# digital_clock_no_resistors.net
KiCad netlist of a schematic drawn in EasyEDA
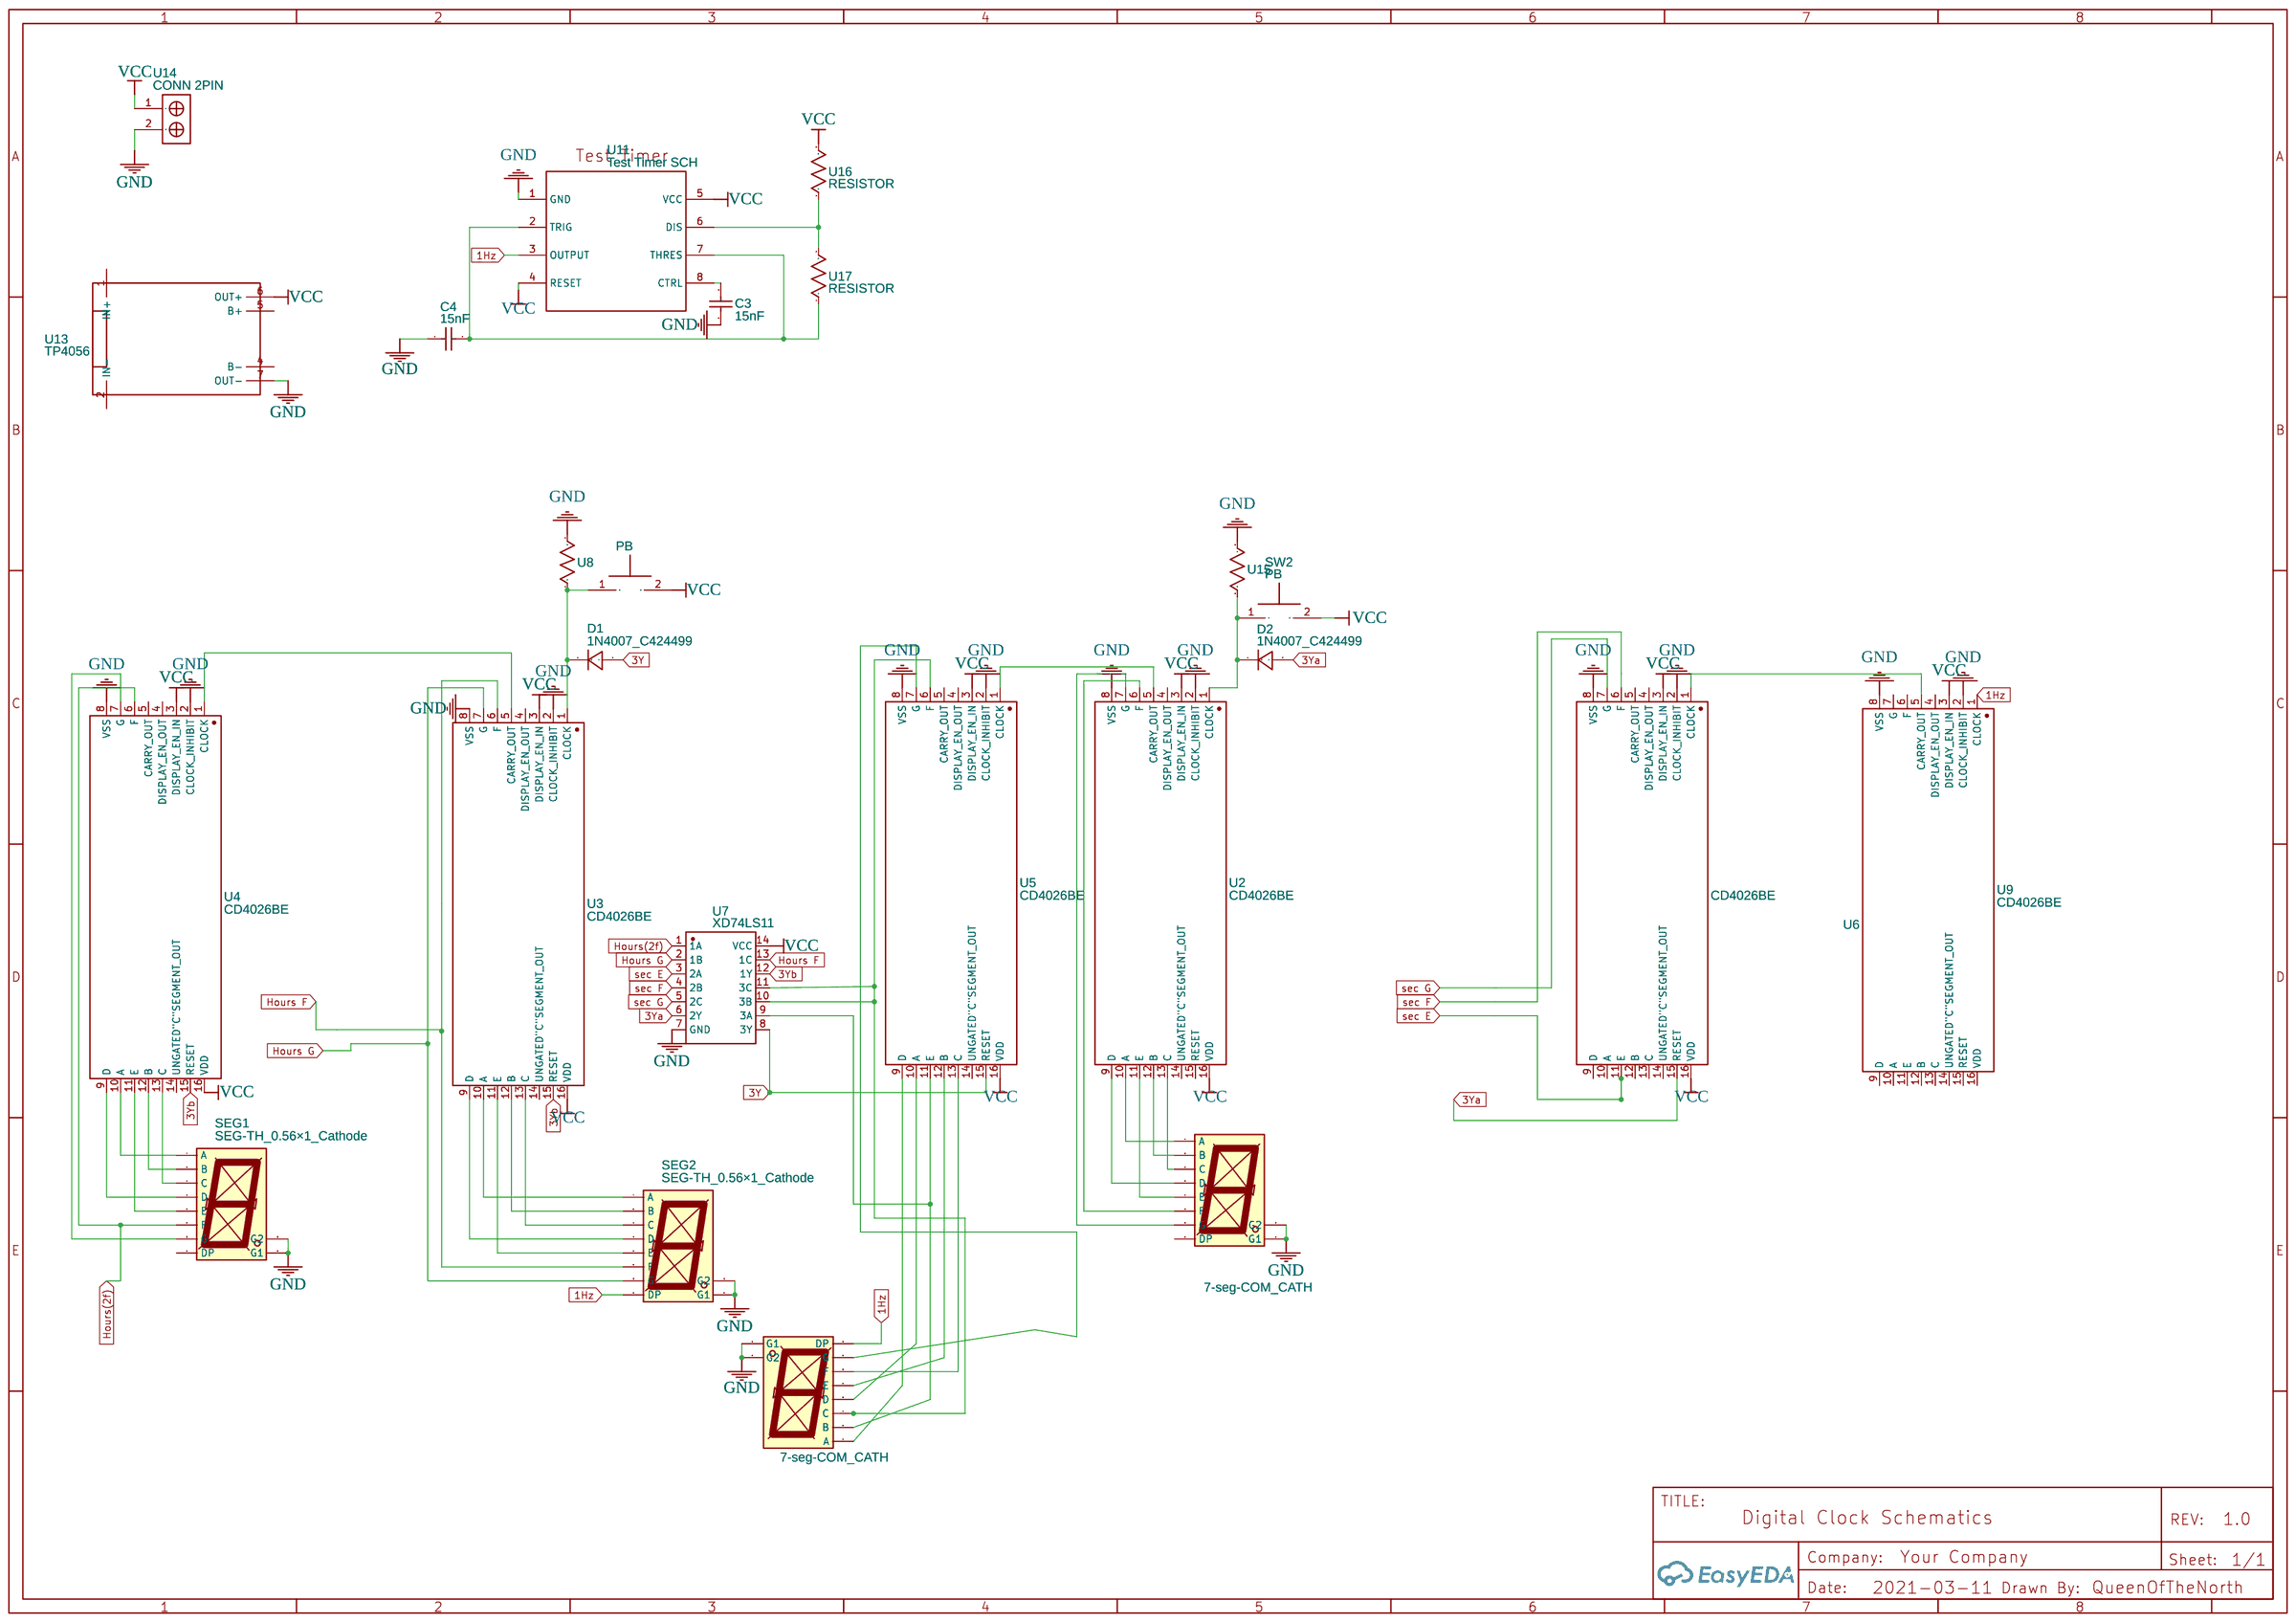
[diagram p0: schematic sheet]

(export (version "E")
  (design (tool "Eeschema 10.0.6"))
  (components
    (comp (ref "C3")
      (value "15nF")
      (fields
        (field (name "BOM_Manufacturer Part") "Capacitor15nf100v")
        (field (name "BOM_Supplier Part") "C26191")
      )
      (libsource (lib "") (part "CAPACITOR15NF100V"))
    )
    (comp (ref "C4")
      (value "15nF")
      (fields
        (field (name "BOM_Manufacturer Part") "Capacitor15nf100v")
        (field (name "BOM_Supplier Part") "C26191")
      )
      (libsource (lib "") (part "CAPACITOR15NF100V_1"))
    )
    (comp (ref "D1")
      (value "1N4007_C424499")
      (fields (field (name "BOM_Manufacturer Part") "1N4007") (field (name "BOM_Supplier Part") "C424499"))
      (libsource (lib "") (part "1N4007_C424499"))
    )
    (comp (ref "D2")
      (value "1N4007_C424499")
      (fields (field (name "BOM_Manufacturer Part") "1N4007") (field (name "BOM_Supplier Part") "C424499"))
      (libsource (lib "") (part "1N4007_C424499"))
    )
    (comp (ref "SEG1")
      (value "SEG-TH_0.56×1_Cathode")
      (fields (field (name "BOM_Supplier Part") "C8093"))
      (libsource (lib "") (part "SEG-TH_0.56×1_Cathode_1"))
    )
    (comp (ref "SEG2")
      (value "SEG-TH_0.56×1_Cathode")
      (fields (field (name "BOM_Supplier Part") "C8093"))
      (libsource (lib "") (part "SEG-TH_0.56×1_Cathode_1"))
    )
    (comp (ref "SEG3")
      (value "7-seg-COM_CATH")
      (fields (field (name "BOM_Supplier Part") "C8093"))
      (libsource (lib "") (part "SEG-TH_0.56×1_Cathode"))
    )
    (comp (ref "SEG4")
      (value "7-seg-COM_CATH")
      (fields (field (name "BOM_Supplier Part") "C8093"))
      (libsource (lib "") (part "SEG-TH_0.56×1_Cathode_1"))
    )
    (comp (ref "SW1")
      (value "PB")
      (fields (field (name "BOM_Manufacturer Part") "Push button"))
      (libsource (lib "") (part "PB"))
    )
    (comp (ref "SW2")
      (value "PB")
      (fields (field (name "BOM_Manufacturer Part") "Push button"))
      (libsource (lib "") (part "PB"))
    )
    (comp (ref "U2")
      (value "CD4026BE")
      (fields (field (name "BOM_Supplier Part") "C89909"))
      (libsource (lib "") (part "CD4026BE"))
    )
    (comp (ref "U3")
      (value "CD4026BE")
      (fields (field (name "BOM_Supplier Part") "C89909"))
      (libsource (lib "") (part "CD4026BE"))
    )
    (comp (ref "U4")
      (value "CD4026BE")
      (fields (field (name "BOM_Supplier Part") "C89909"))
      (libsource (lib "") (part "CD4026BE"))
    )
    (comp (ref "U5")
      (value "CD4026BE")
      (fields (field (name "BOM_Supplier Part") "C89909"))
      (libsource (lib "") (part "CD4026BE"))
    )
    (comp (ref "U6")
      (value "CD4026BE")
      (fields (field (name "BOM_Supplier Part") "C89909"))
      (libsource (lib "") (part "CD4026BE"))
    )
    (comp (ref "U7")
      (value "XD74LS11")
      (fields (field (name "BOM_Supplier Part") "C521167"))
      (libsource (lib "") (part "XD74LS11"))
    )
    (comp (ref "U8")
      (value "RESISTOR")
      (fields (field (name "BOM_Manufacturer Part") "0.4W 1% RESISTOR"))
      (libsource (lib "") (part "RESISTOR"))
    )
    (comp (ref "U9")
      (value "CD4026BE")
      (fields (field (name "BOM_Supplier Part") "C89909"))
      (libsource (lib "") (part "CD4026BE"))
    )
    (comp (ref "U11")
      (value "Test Timer SCH")
      (fields (field (name "BOM_Manufacturer Part") "555 Timer"))
      (libsource (lib "") (part "Test Timer SCH"))
    )
    (comp (ref "U13")
      (value "TP4056")
      (fields (field (name "BOM_Manufacturer Part") "TP4056-protect"))
      (libsource (lib "") (part "TP4056"))
    )
    (comp (ref "U14")
      (value "CONN 2PIN")
      (fields
        (field (name "BOM_Manufacturer Part") "Terminal Block")
        (field (name "BOM_Supplier Part") "undefined")
      )
      (libsource (lib "") (part "CONN 2PIN"))
    )
    (comp (ref "U15")
      (value "RESISTOR")
      (fields (field (name "BOM_Manufacturer Part") "0.4W 1% RESISTOR"))
      (libsource (lib "") (part "RESISTOR"))
    )
    (comp (ref "U16")
      (value "RESISTOR")
      (fields (field (name "BOM_Manufacturer Part") "0.4W 1% RESISTOR"))
      (libsource (lib "") (part "RESISTOR"))
    )
    (comp (ref "U17")
      (value "RESISTOR")
      (fields (field (name "BOM_Manufacturer Part") "0.4W 1% RESISTOR"))
      (libsource (lib "") (part "RESISTOR"))
    )
  )
  (nets
    (net (code "1") (name "1Hz") (class "Default")
      (node (ref "SEG2") (pin "5") (pinfunction "DP_5") (pintype "unspecified"))
      (node (ref "SEG3") (pin "5") (pinfunction "DP_5") (pintype "unspecified"))
      (node (ref "U11") (pin "3") (pinfunction "OUTPUT_3") (pintype "unspecified"))
      (node (ref "U9") (pin "1") (pinfunction "CLOCK_1") (pintype "unspecified"))
    )
    (net (code "2") (name "3Y") (class "Default")
      (node (ref "D1") (pin "2") (pinfunction "A_2") (pintype "unspecified"))
      (node (ref "U5") (pin "15") (pinfunction "RESET_15") (pintype "unspecified"))
      (node (ref "U7") (pin "8") (pinfunction "3Y_8") (pintype "unspecified"))
    )
    (net (code "3") (name "3Ya") (class "Default")
      (node (ref "D2") (pin "2") (pinfunction "A_2") (pintype "unspecified"))
      (node (ref "U6") (pin "15") (pinfunction "RESET_15") (pintype "unspecified"))
      (node (ref "U7") (pin "6") (pinfunction "2Y_6") (pintype "unspecified"))
    )
    (net (code "4") (name "3Yb") (class "Default")
      (node (ref "U3") (pin "15") (pinfunction "RESET_15") (pintype "unspecified"))
      (node (ref "U4") (pin "15") (pinfunction "RESET_15") (pintype "unspecified"))
      (node (ref "U7") (pin "12") (pinfunction "1Y_12") (pintype "unspecified"))
    )
    (net (code "5") (name "GND") (class "Default")
      (node (ref "C3") (pin "1") (pinfunction "1_1") (pintype "input"))
      (node (ref "C4") (pin "1") (pinfunction "1_1") (pintype "input"))
      (node (ref "SEG1") (pin "3") (pinfunction "G1_3") (pintype "unspecified"))
      (node (ref "SEG1") (pin "8") (pinfunction "G2_8") (pintype "unspecified"))
      (node (ref "SEG2") (pin "3") (pinfunction "G1_3") (pintype "unspecified"))
      (node (ref "SEG2") (pin "8") (pinfunction "G2_8") (pintype "unspecified"))
      (node (ref "SEG3") (pin "3") (pinfunction "G1_3") (pintype "unspecified"))
      (node (ref "SEG3") (pin "8") (pinfunction "G2_8") (pintype "unspecified"))
      (node (ref "SEG4") (pin "3") (pinfunction "G1_3") (pintype "unspecified"))
      (node (ref "SEG4") (pin "8") (pinfunction "G2_8") (pintype "unspecified"))
      (node (ref "U11") (pin "1") (pinfunction "GND_1") (pintype "unspecified"))
      (node (ref "U13") (pin "7") (pinfunction "OUT-_7") (pintype "unspecified"))
      (node (ref "U14") (pin "2") (pinfunction "2_2") (pintype "unspecified"))
      (node (ref "U15") (pin "2") (pinfunction "2_2") (pintype "unspecified"))
      (node (ref "U2") (pin "2") (pinfunction "CLOCK_INHIBIT_2") (pintype "unspecified"))
      (node (ref "U2") (pin "8") (pinfunction "VSS_8") (pintype "unspecified"))
      (node (ref "U3") (pin "2") (pinfunction "CLOCK_INHIBIT_2") (pintype "unspecified"))
      (node (ref "U3") (pin "8") (pinfunction "VSS_8") (pintype "unspecified"))
      (node (ref "U4") (pin "2") (pinfunction "CLOCK_INHIBIT_2") (pintype "unspecified"))
      (node (ref "U4") (pin "8") (pinfunction "VSS_8") (pintype "unspecified"))
      (node (ref "U5") (pin "2") (pinfunction "CLOCK_INHIBIT_2") (pintype "unspecified"))
      (node (ref "U5") (pin "8") (pinfunction "VSS_8") (pintype "unspecified"))
      (node (ref "U6") (pin "2") (pinfunction "CLOCK_INHIBIT_2") (pintype "unspecified"))
      (node (ref "U6") (pin "8") (pinfunction "VSS_8") (pintype "unspecified"))
      (node (ref "U7") (pin "7") (pinfunction "GND_7") (pintype "unspecified"))
      (node (ref "U8") (pin "2") (pinfunction "2_2") (pintype "unspecified"))
      (node (ref "U9") (pin "2") (pinfunction "CLOCK_INHIBIT_2") (pintype "unspecified"))
      (node (ref "U9") (pin "8") (pinfunction "VSS_8") (pintype "unspecified"))
    )
    (net (code "6") (name "Hours F") (class "Default")
      (node (ref "SEG2") (pin "9") (pinfunction "F_9") (pintype "unspecified"))
      (node (ref "U3") (pin "6") (pinfunction "F_6") (pintype "unspecified"))
      (node (ref "U7") (pin "13") (pinfunction "1C_13") (pintype "unspecified"))
    )
    (net (code "7") (name "Hours G") (class "Default")
      (node (ref "SEG2") (pin "10") (pinfunction "G_10") (pintype "unspecified"))
      (node (ref "U3") (pin "7") (pinfunction "G_7") (pintype "unspecified"))
      (node (ref "U7") (pin "2") (pinfunction "1B_2") (pintype "unspecified"))
    )
    (net (code "8") (name "Hours(2f)") (class "Default")
      (node (ref "SEG1") (pin "9") (pinfunction "F_9") (pintype "unspecified"))
      (node (ref "U4") (pin "6") (pinfunction "F_6") (pintype "unspecified"))
      (node (ref "U7") (pin "1") (pinfunction "1A_1") (pintype "unspecified"))
    )
    (net (code "9") (name "Net-(D1-C)") (class "Default")
      (node (ref "D1") (pin "1") (pinfunction "C_1") (pintype "unspecified"))
      (node (ref "SW1") (pin "1") (pinfunction "1_1") (pintype "unspecified"))
      (node (ref "U3") (pin "1") (pinfunction "CLOCK_1") (pintype "unspecified"))
      (node (ref "U8") (pin "1") (pinfunction "1_1") (pintype "unspecified"))
    )
    (net (code "10") (name "Net-(D2-C)") (class "Default")
      (node (ref "D2") (pin "1") (pinfunction "C_1") (pintype "unspecified"))
      (node (ref "SW2") (pin "1") (pinfunction "1_1") (pintype "unspecified"))
      (node (ref "U15") (pin "1") (pinfunction "1_1") (pintype "unspecified"))
      (node (ref "U2") (pin "1") (pinfunction "CLOCK_1") (pintype "unspecified"))
    )
    (net (code "11") (name "Net-(SEG1-A)") (class "Default")
      (node (ref "SEG1") (pin "7") (pinfunction "A_7") (pintype "unspecified"))
      (node (ref "U4") (pin "10") (pinfunction "A_10") (pintype "unspecified"))
    )
    (net (code "12") (name "Net-(SEG1-B)") (class "Default")
      (node (ref "SEG1") (pin "6") (pinfunction "B_6") (pintype "unspecified"))
      (node (ref "U4") (pin "12") (pinfunction "B_12") (pintype "unspecified"))
    )
    (net (code "13") (name "Net-(SEG1-C)") (class "Default")
      (node (ref "SEG1") (pin "4") (pinfunction "C_4") (pintype "unspecified"))
      (node (ref "U4") (pin "13") (pinfunction "C_13") (pintype "unspecified"))
    )
    (net (code "14") (name "Net-(SEG1-D)") (class "Default")
      (node (ref "SEG1") (pin "2") (pinfunction "D_2") (pintype "unspecified"))
      (node (ref "U4") (pin "9") (pinfunction "D_9") (pintype "unspecified"))
    )
    (net (code "15") (name "Net-(SEG1-E)") (class "Default")
      (node (ref "SEG1") (pin "1") (pinfunction "E_1") (pintype "unspecified"))
      (node (ref "U4") (pin "11") (pinfunction "E_11") (pintype "unspecified"))
    )
    (net (code "16") (name "Net-(SEG1-G)") (class "Default")
      (node (ref "SEG1") (pin "10") (pinfunction "G_10") (pintype "unspecified"))
      (node (ref "U4") (pin "7") (pinfunction "G_7") (pintype "unspecified"))
    )
    (net (code "17") (name "Net-(SEG2-A)") (class "Default")
      (node (ref "SEG2") (pin "7") (pinfunction "A_7") (pintype "unspecified"))
      (node (ref "U3") (pin "10") (pinfunction "A_10") (pintype "unspecified"))
    )
    (net (code "18") (name "Net-(SEG2-B)") (class "Default")
      (node (ref "SEG2") (pin "6") (pinfunction "B_6") (pintype "unspecified"))
      (node (ref "U3") (pin "12") (pinfunction "B_12") (pintype "unspecified"))
    )
    (net (code "19") (name "Net-(SEG2-C)") (class "Default")
      (node (ref "SEG2") (pin "4") (pinfunction "C_4") (pintype "unspecified"))
      (node (ref "U3") (pin "13") (pinfunction "C_13") (pintype "unspecified"))
    )
    (net (code "20") (name "Net-(SEG2-D)") (class "Default")
      (node (ref "SEG2") (pin "2") (pinfunction "D_2") (pintype "unspecified"))
      (node (ref "U3") (pin "9") (pinfunction "D_9") (pintype "unspecified"))
    )
    (net (code "21") (name "Net-(SEG2-E)") (class "Default")
      (node (ref "SEG2") (pin "1") (pinfunction "E_1") (pintype "unspecified"))
      (node (ref "U3") (pin "11") (pinfunction "E_11") (pintype "unspecified"))
    )
    (net (code "22") (name "Net-(SEG3-A)") (class "Default")
      (node (ref "SEG3") (pin "7") (pinfunction "A_7") (pintype "unspecified"))
      (node (ref "U5") (pin "9") (pinfunction "D_9") (pintype "unspecified"))
    )
    (net (code "23") (name "Net-(SEG3-B)") (class "Default")
      (node (ref "SEG3") (pin "6") (pinfunction "B_6") (pintype "unspecified"))
      (node (ref "U5") (pin "11") (pinfunction "E_11") (pintype "unspecified"))
      (node (ref "U7") (pin "9") (pinfunction "3A_9") (pintype "unspecified"))
    )
    (net (code "24") (name "Net-(SEG3-C)") (class "Default")
      (node (ref "SEG3") (pin "4") (pinfunction "C_4") (pintype "unspecified"))
      (node (ref "U5") (pin "6") (pinfunction "F_6") (pintype "unspecified"))
      (node (ref "U7") (pin "10") (pinfunction "3B_10") (pintype "unspecified"))
      (node (ref "U7") (pin "11") (pinfunction "3C_11") (pintype "unspecified"))
    )
    (net (code "25") (name "Net-(SEG3-D)") (class "Default")
      (node (ref "SEG3") (pin "2") (pinfunction "D_2") (pintype "unspecified"))
      (node (ref "U5") (pin "10") (pinfunction "A_10") (pintype "unspecified"))
    )
    (net (code "26") (name "Net-(SEG3-E)") (class "Default")
      (node (ref "SEG3") (pin "1") (pinfunction "E_1") (pintype "unspecified"))
      (node (ref "U5") (pin "12") (pinfunction "B_12") (pintype "unspecified"))
    )
    (net (code "27") (name "Net-(SEG3-F)") (class "Default")
      (node (ref "SEG3") (pin "9") (pinfunction "F_9") (pintype "unspecified"))
      (node (ref "U5") (pin "13") (pinfunction "C_13") (pintype "unspecified"))
    )
    (net (code "28") (name "Net-(SEG3-G)") (class "Default")
      (node (ref "SEG3") (pin "10") (pinfunction "G_10") (pintype "unspecified"))
      (node (ref "U5") (pin "7") (pinfunction "G_7") (pintype "unspecified"))
    )
    (net (code "29") (name "Net-(SEG4-A)") (class "Default")
      (node (ref "SEG4") (pin "7") (pinfunction "A_7") (pintype "unspecified"))
      (node (ref "U2") (pin "10") (pinfunction "A_10") (pintype "unspecified"))
    )
    (net (code "30") (name "Net-(SEG4-B)") (class "Default")
      (node (ref "SEG4") (pin "6") (pinfunction "B_6") (pintype "unspecified"))
      (node (ref "U2") (pin "12") (pinfunction "B_12") (pintype "unspecified"))
    )
    (net (code "31") (name "Net-(SEG4-C)") (class "Default")
      (node (ref "SEG4") (pin "4") (pinfunction "C_4") (pintype "unspecified"))
      (node (ref "U2") (pin "13") (pinfunction "C_13") (pintype "unspecified"))
    )
    (net (code "32") (name "Net-(SEG4-D)") (class "Default")
      (node (ref "SEG4") (pin "2") (pinfunction "D_2") (pintype "unspecified"))
      (node (ref "U2") (pin "9") (pinfunction "D_9") (pintype "unspecified"))
    )
    (net (code "33") (name "Net-(SEG4-E)") (class "Default")
      (node (ref "SEG4") (pin "1") (pinfunction "E_1") (pintype "unspecified"))
      (node (ref "U2") (pin "11") (pinfunction "E_11") (pintype "unspecified"))
    )
    (net (code "34") (name "Net-(SEG4-F)") (class "Default")
      (node (ref "SEG4") (pin "9") (pinfunction "F_9") (pintype "unspecified"))
      (node (ref "U2") (pin "6") (pinfunction "F_6") (pintype "unspecified"))
    )
    (net (code "35") (name "Net-(SEG4-G)") (class "Default")
      (node (ref "SEG4") (pin "10") (pinfunction "G_10") (pintype "unspecified"))
      (node (ref "U2") (pin "7") (pinfunction "G_7") (pintype "unspecified"))
    )
    (net (code "36") (name "Net-(U2-CARRY_OUT)") (class "Default")
      (node (ref "U2") (pin "5") (pinfunction "CARRY_OUT_5") (pintype "unspecified"))
      (node (ref "U5") (pin "1") (pinfunction "CLOCK_1") (pintype "unspecified"))
    )
    (net (code "37") (name "Net-(U3-CARRY_OUT)") (class "Default")
      (node (ref "U3") (pin "5") (pinfunction "CARRY_OUT_5") (pintype "unspecified"))
      (node (ref "U4") (pin "1") (pinfunction "CLOCK_1") (pintype "unspecified"))
    )
    (net (code "38") (name "Net-(U6-CLOCK)") (class "Default")
      (node (ref "U6") (pin "1") (pinfunction "CLOCK_1") (pintype "unspecified"))
      (node (ref "U9") (pin "5") (pinfunction "CARRY_OUT_5") (pintype "unspecified"))
    )
    (net (code "39") (name "Net-(U11-CTRL)") (class "Default")
      (node (ref "C3") (pin "2") (pinfunction "2_2") (pintype "input"))
      (node (ref "U11") (pin "8") (pinfunction "CTRL_8") (pintype "unspecified"))
    )
    (net (code "40") (name "Net-(U11-DIS)") (class "Default")
      (node (ref "U11") (pin "6") (pinfunction "DIS_6") (pintype "unspecified"))
      (node (ref "U16") (pin "1") (pinfunction "1_1") (pintype "unspecified"))
      (node (ref "U17") (pin "2") (pinfunction "2_2") (pintype "unspecified"))
    )
    (net (code "41") (name "Net-(U11-THRES)") (class "Default")
      (node (ref "C4") (pin "2") (pinfunction "2_2") (pintype "input"))
      (node (ref "U11") (pin "2") (pinfunction "TRIG_2") (pintype "unspecified"))
      (node (ref "U11") (pin "7") (pinfunction "THRES_7") (pintype "unspecified"))
      (node (ref "U17") (pin "1") (pinfunction "1_1") (pintype "unspecified"))
    )
    (net (code "42") (name "VCC") (class "Default")
      (node (ref "SW1") (pin "2") (pinfunction "2_2") (pintype "unspecified"))
      (node (ref "SW2") (pin "2") (pinfunction "2_2") (pintype "unspecified"))
      (node (ref "U11") (pin "4") (pinfunction "RESET_4") (pintype "unspecified"))
      (node (ref "U11") (pin "5") (pinfunction "VCC_5") (pintype "unspecified"))
      (node (ref "U13") (pin "6") (pinfunction "OUT+_6") (pintype "unspecified"))
      (node (ref "U14") (pin "1") (pinfunction "1_1") (pintype "unspecified"))
      (node (ref "U16") (pin "2") (pinfunction "2_2") (pintype "unspecified"))
      (node (ref "U2") (pin "16") (pinfunction "VDD_16") (pintype "unspecified"))
      (node (ref "U2") (pin "3") (pinfunction "DISPLAY_EN_IN_3") (pintype "unspecified"))
      (node (ref "U3") (pin "16") (pinfunction "VDD_16") (pintype "unspecified"))
      (node (ref "U3") (pin "3") (pinfunction "DISPLAY_EN_IN_3") (pintype "unspecified"))
      (node (ref "U4") (pin "16") (pinfunction "VDD_16") (pintype "unspecified"))
      (node (ref "U4") (pin "3") (pinfunction "DISPLAY_EN_IN_3") (pintype "unspecified"))
      (node (ref "U5") (pin "16") (pinfunction "VDD_16") (pintype "unspecified"))
      (node (ref "U5") (pin "3") (pinfunction "DISPLAY_EN_IN_3") (pintype "unspecified"))
      (node (ref "U6") (pin "16") (pinfunction "VDD_16") (pintype "unspecified"))
      (node (ref "U6") (pin "3") (pinfunction "DISPLAY_EN_IN_3") (pintype "unspecified"))
      (node (ref "U7") (pin "14") (pinfunction "VCC_14") (pintype "unspecified"))
      (node (ref "U9") (pin "3") (pinfunction "DISPLAY_EN_IN_3") (pintype "unspecified"))
    )
    (net (code "43") (name "sec E") (class "Default")
      (node (ref "U6") (pin "11") (pinfunction "E_11") (pintype "unspecified"))
      (node (ref "U7") (pin "3") (pinfunction "2A_3") (pintype "unspecified"))
    )
    (net (code "44") (name "sec F") (class "Default")
      (node (ref "U6") (pin "6") (pinfunction "F_6") (pintype "unspecified"))
      (node (ref "U7") (pin "4") (pinfunction "2B_4") (pintype "unspecified"))
    )
    (net (code "45") (name "sec G") (class "Default")
      (node (ref "U6") (pin "7") (pinfunction "G_7") (pintype "unspecified"))
      (node (ref "U7") (pin "5") (pinfunction "2C_5") (pintype "unspecified"))
    )
    (net (code "46") (name "unconnected-(SEG1-DP-Pad5)") (class "Default")
      (node (ref "SEG1") (pin "5") (pinfunction "DP_5") (pintype "unspecified"))
    )
    (net (code "47") (name "unconnected-(SEG4-DP-Pad5)") (class "Default")
      (node (ref "SEG4") (pin "5") (pinfunction "DP_5") (pintype "unspecified"))
    )
    (net (code "48") (name "unconnected-(U2-DISPLAY_EN_OUT-Pad4)") (class "Default")
      (node (ref "U2") (pin "4") (pinfunction "DISPLAY_EN_OUT_4") (pintype "unspecified"))
    )
    (net (code "49") (name "unconnected-(U2-RESET-Pad15)") (class "Default")
      (node (ref "U2") (pin "15") (pinfunction "RESET_15") (pintype "unspecified"))
    )
    (net (code "50") (name "unconnected-(U2-UNGATED\"C\"SEGMENT_OUT-Pad14)") (class "Default")
      (node (ref "U2") (pin "14") (pinfunction "UNGATED\"C\"SEGMENT_OUT_14") (pintype "unspecified"))
    )
    (net (code "51") (name "unconnected-(U3-DISPLAY_EN_OUT-Pad4)") (class "Default")
      (node (ref "U3") (pin "4") (pinfunction "DISPLAY_EN_OUT_4") (pintype "unspecified"))
    )
    (net (code "52") (name "unconnected-(U3-UNGATED\"C\"SEGMENT_OUT-Pad14)") (class "Default")
      (node (ref "U3") (pin "14") (pinfunction "UNGATED\"C\"SEGMENT_OUT_14") (pintype "unspecified"))
    )
    (net (code "53") (name "unconnected-(U4-CARRY_OUT-Pad5)") (class "Default")
      (node (ref "U4") (pin "5") (pinfunction "CARRY_OUT_5") (pintype "unspecified"))
    )
    (net (code "54") (name "unconnected-(U4-DISPLAY_EN_OUT-Pad4)") (class "Default")
      (node (ref "U4") (pin "4") (pinfunction "DISPLAY_EN_OUT_4") (pintype "unspecified"))
    )
    (net (code "55") (name "unconnected-(U4-UNGATED\"C\"SEGMENT_OUT-Pad14)") (class "Default")
      (node (ref "U4") (pin "14") (pinfunction "UNGATED\"C\"SEGMENT_OUT_14") (pintype "unspecified"))
    )
    (net (code "56") (name "unconnected-(U5-CARRY_OUT-Pad5)") (class "Default")
      (node (ref "U5") (pin "5") (pinfunction "CARRY_OUT_5") (pintype "unspecified"))
    )
    (net (code "57") (name "unconnected-(U5-DISPLAY_EN_OUT-Pad4)") (class "Default")
      (node (ref "U5") (pin "4") (pinfunction "DISPLAY_EN_OUT_4") (pintype "unspecified"))
    )
    (net (code "58") (name "unconnected-(U5-UNGATED\"C\"SEGMENT_OUT-Pad14)") (class "Default")
      (node (ref "U5") (pin "14") (pinfunction "UNGATED\"C\"SEGMENT_OUT_14") (pintype "unspecified"))
    )
    (net (code "59") (name "unconnected-(U6-A-Pad10)") (class "Default")
      (node (ref "U6") (pin "10") (pinfunction "A_10") (pintype "unspecified"))
    )
    (net (code "60") (name "unconnected-(U6-B-Pad12)") (class "Default")
      (node (ref "U6") (pin "12") (pinfunction "B_12") (pintype "unspecified"))
    )
    (net (code "61") (name "unconnected-(U6-C-Pad13)") (class "Default")
      (node (ref "U6") (pin "13") (pinfunction "C_13") (pintype "unspecified"))
    )
    (net (code "62") (name "unconnected-(U6-CARRY_OUT-Pad5)") (class "Default")
      (node (ref "U6") (pin "5") (pinfunction "CARRY_OUT_5") (pintype "unspecified"))
    )
    (net (code "63") (name "unconnected-(U6-D-Pad9)") (class "Default")
      (node (ref "U6") (pin "9") (pinfunction "D_9") (pintype "unspecified"))
    )
    (net (code "64") (name "unconnected-(U6-DISPLAY_EN_OUT-Pad4)") (class "Default")
      (node (ref "U6") (pin "4") (pinfunction "DISPLAY_EN_OUT_4") (pintype "unspecified"))
    )
    (net (code "65") (name "unconnected-(U6-UNGATED\"C\"SEGMENT_OUT-Pad14)") (class "Default")
      (node (ref "U6") (pin "14") (pinfunction "UNGATED\"C\"SEGMENT_OUT_14") (pintype "unspecified"))
    )
    (net (code "66") (name "unconnected-(U9-A-Pad10)") (class "Default")
      (node (ref "U9") (pin "10") (pinfunction "A_10") (pintype "unspecified"))
    )
    (net (code "67") (name "unconnected-(U9-B-Pad12)") (class "Default")
      (node (ref "U9") (pin "12") (pinfunction "B_12") (pintype "unspecified"))
    )
    (net (code "68") (name "unconnected-(U9-C-Pad13)") (class "Default")
      (node (ref "U9") (pin "13") (pinfunction "C_13") (pintype "unspecified"))
    )
    (net (code "69") (name "unconnected-(U9-D-Pad9)") (class "Default")
      (node (ref "U9") (pin "9") (pinfunction "D_9") (pintype "unspecified"))
    )
    (net (code "70") (name "unconnected-(U9-DISPLAY_EN_OUT-Pad4)") (class "Default")
      (node (ref "U9") (pin "4") (pinfunction "DISPLAY_EN_OUT_4") (pintype "unspecified"))
    )
    (net (code "71") (name "unconnected-(U9-E-Pad11)") (class "Default")
      (node (ref "U9") (pin "11") (pinfunction "E_11") (pintype "unspecified"))
    )
    (net (code "72") (name "unconnected-(U9-F-Pad6)") (class "Default")
      (node (ref "U9") (pin "6") (pinfunction "F_6") (pintype "unspecified"))
    )
    (net (code "73") (name "unconnected-(U9-G-Pad7)") (class "Default")
      (node (ref "U9") (pin "7") (pinfunction "G_7") (pintype "unspecified"))
    )
    (net (code "74") (name "unconnected-(U9-RESET-Pad15)") (class "Default")
      (node (ref "U9") (pin "15") (pinfunction "RESET_15") (pintype "unspecified"))
    )
    (net (code "75") (name "unconnected-(U9-UNGATED\"C\"SEGMENT_OUT-Pad14)") (class "Default")
      (node (ref "U9") (pin "14") (pinfunction "UNGATED\"C\"SEGMENT_OUT_14") (pintype "unspecified"))
    )
    (net (code "76") (name "unconnected-(U9-VDD-Pad16)") (class "Default")
      (node (ref "U9") (pin "16") (pinfunction "VDD_16") (pintype "unspecified"))
    )
    (net (code "77") (name "unconnected-(U13-B+-Pad5)") (class "Default")
      (node (ref "U13") (pin "5") (pinfunction "B+_5") (pintype "unspecified"))
    )
    (net (code "78") (name "unconnected-(U13-B--Pad4)") (class "Default")
      (node (ref "U13") (pin "4") (pinfunction "B-_4") (pintype "unspecified"))
    )
    (net (code "79") (name "unconnected-(U13-IN+-Pad1)") (class "Default")
      (node (ref "U13") (pin "1") (pinfunction "IN+_1") (pintype "unspecified"))
    )
    (net (code "80") (name "unconnected-(U13-IN--Pad2)") (class "Default")
      (node (ref "U13") (pin "2") (pinfunction "IN-_2") (pintype "unspecified"))
    )
  )
)
